# amiga-pcb-led.net
KiCad netlist of a schematic drawn in EAGLE
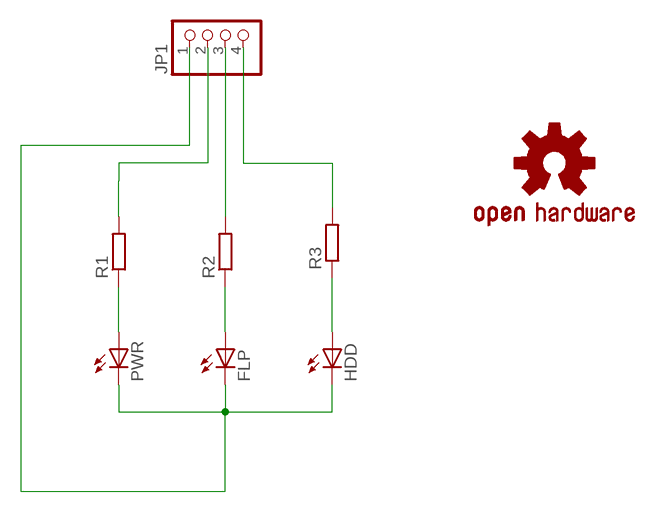
[diagram p0: schematic, sheet 1]

(export (version "E")
  (design (tool "Eeschema 10.0.6"))
  (components
    (comp (ref "FLP")
      (value "LEDSQR2X5")
      (footprint "eagle-import:LED2X5")
      (libsource (lib "eagle-import") (part "LEDSQR2X5"))
    )
    (comp (ref "HDD")
      (value "LEDSQR2X5")
      (footprint "eagle-import:LED2X5")
      (libsource (lib "eagle-import") (part "LEDSQR2X5"))
    )
    (comp (ref "JP1")
      (value "PINHD-1X4")
      (footprint "eagle-import:1X04")
      (libsource (lib "eagle-import") (part "PINHD-1X4"))
    )
    (comp (ref "LOGO2")
      (value "OSHW-LOGOS-COPPER")
      (footprint "eagle-import:OSHW-LOGO-S_COPPER")
      (libsource (lib "eagle-import") (part "OSHW-LOGOS-COPPER"))
    )
    (comp (ref "PWR")
      (value "LEDSQR2X5")
      (footprint "eagle-import:LED2X5")
      (libsource (lib "eagle-import") (part "LEDSQR2X5"))
    )
    (comp (ref "R1")
      (value "R-EU_R0603")
      (footprint "eagle-import:R0603")
      (libsource (lib "eagle-import") (part "R-EU_R0603"))
    )
    (comp (ref "R2")
      (value "R-EU_R0603")
      (footprint "eagle-import:R0603")
      (libsource (lib "eagle-import") (part "R-EU_R0603"))
    )
    (comp (ref "R3")
      (value "R-EU_R0603")
      (footprint "eagle-import:R0603")
      (libsource (lib "eagle-import") (part "R-EU_R0603"))
    )
  )
  (nets
    (net (code "1") (name "Net-(FLP-C)") (class "Default")
      (node (ref "FLP") (pin "K") (pinfunction "C_K") (pintype "passive"))
      (node (ref "HDD") (pin "K") (pinfunction "C_K") (pintype "passive"))
      (node (ref "JP1") (pin "1") (pinfunction "1_1") (pintype "passive"))
      (node (ref "PWR") (pin "K") (pinfunction "C_K") (pintype "passive"))
    )
    (net (code "2") (name "Net-(FLP-PadA)") (class "Default")
      (node (ref "FLP") (pin "A") (pinfunction "A_A") (pintype "passive"))
      (node (ref "R2") (pin "1") (pinfunction "1_1") (pintype "passive"))
    )
    (net (code "3") (name "Net-(HDD-PadA)") (class "Default")
      (node (ref "HDD") (pin "A") (pinfunction "A_A") (pintype "passive"))
      (node (ref "R3") (pin "1") (pinfunction "1_1") (pintype "passive"))
    )
    (net (code "4") (name "Net-(JP1-Pad2)") (class "Default")
      (node (ref "JP1") (pin "2") (pinfunction "2_2") (pintype "passive"))
      (node (ref "R1") (pin "2") (pinfunction "2_2") (pintype "passive"))
    )
    (net (code "5") (name "Net-(JP1-Pad3)") (class "Default")
      (node (ref "JP1") (pin "3") (pinfunction "3_3") (pintype "passive"))
      (node (ref "R2") (pin "2") (pinfunction "2_2") (pintype "passive"))
    )
    (net (code "6") (name "Net-(JP1-Pad4)") (class "Default")
      (node (ref "JP1") (pin "4") (pinfunction "4_4") (pintype "passive"))
      (node (ref "R3") (pin "2") (pinfunction "2_2") (pintype "passive"))
    )
    (net (code "7") (name "Net-(PWR-PadA)") (class "Default")
      (node (ref "PWR") (pin "A") (pinfunction "A_A") (pintype "passive"))
      (node (ref "R1") (pin "1") (pinfunction "1_1") (pintype "passive"))
    )
  )
)
